# CoolRoof_Terminal_exterieur.net
KiCad netlist of a schematic drawn in EAGLE
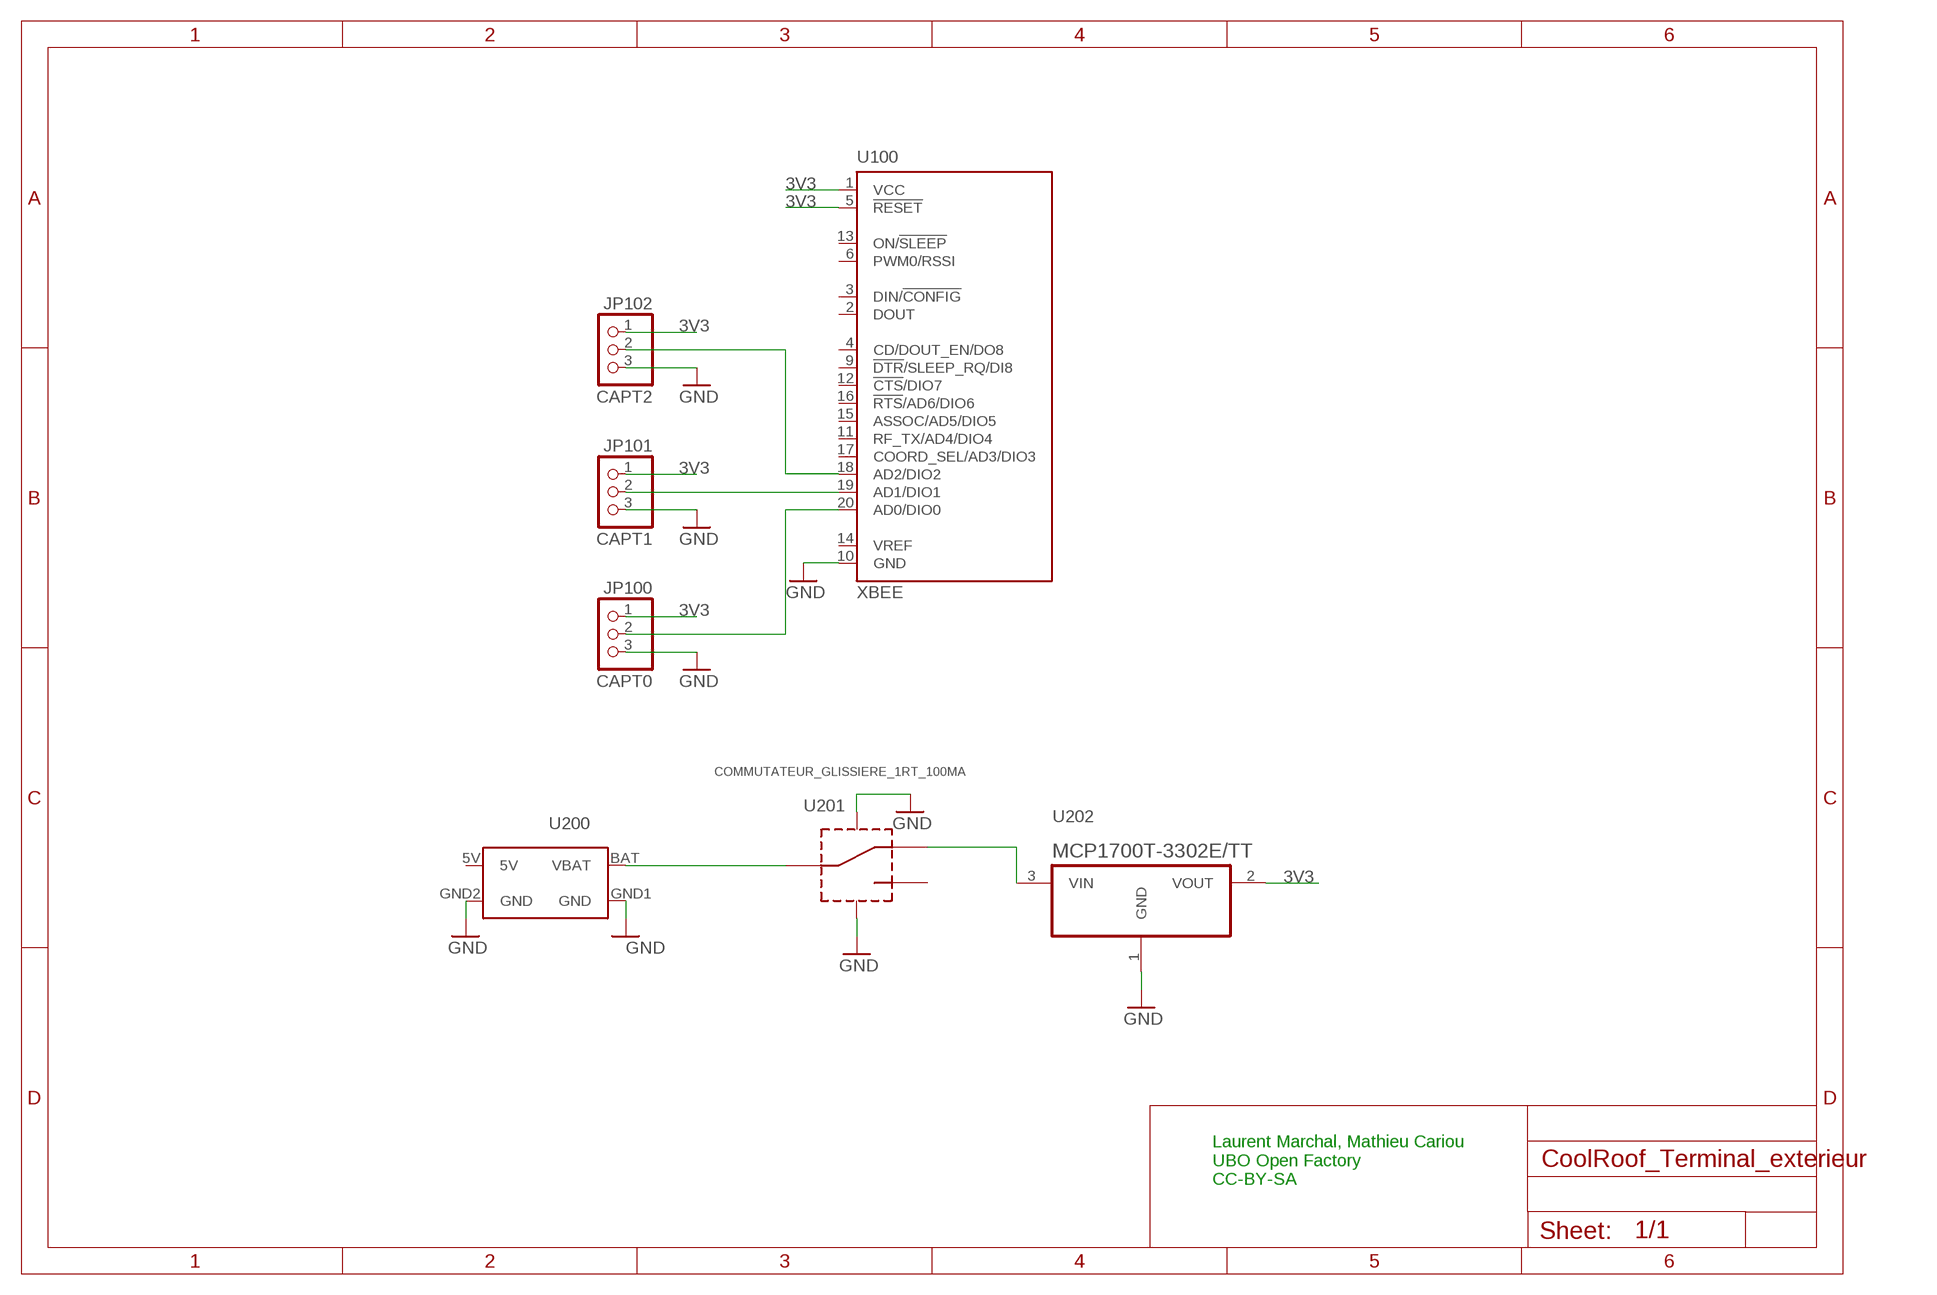
[diagram p0: schematic, sheet 1]

(export (version "E")
  (design (tool "Eeschema 10.0.6"))
  (components
    (comp (ref "JP100")
      (value "CAPT0")
      (footprint "eagle-import:1X03")
      (libsource (lib "eagle-import") (part "PINHD-1X3"))
    )
    (comp (ref "JP101")
      (value "CAPT1")
      (footprint "eagle-import:1X03")
      (libsource (lib "eagle-import") (part "PINHD-1X3"))
    )
    (comp (ref "JP102")
      (value "CAPT2")
      (footprint "eagle-import:1X03")
      (libsource (lib "eagle-import") (part "PINHD-1X3"))
    )
    (comp (ref "U100")
      (value "XBEE")
      (footprint "eagle-import:XBEE")
      (fields (field (name "MPN") "XBP24-Z7UIT-004"))
      (libsource (lib "eagle-import") (part "XBEE"))
    )
    (comp (ref "U200")
      (value "MICROUSB-LIPO-CHARGEUR-ADAFRUITMICRO-USB-CHARGEUR")
      (footprint "eagle-import:MICROUSB-LIPO-CHARGEUR-ADAFRUIT")
      (libsource (lib "eagle-import") (part "MICROUSB-LIPO-CHARGEUR-ADAFRUITMICRO-USB-CHARGEUR"))
    )
    (comp (ref "U201")
      (value "COMMUTATEUR_GLISSIERE_1RT_100MA")
      (footprint "eagle-import:COMMUTATEUR_GLISSIERE_1RT_100MA")
      (libsource (lib "eagle-import") (part "COMMUTATEUR_GLISSIERE_1RT_100MA"))
    )
    (comp (ref "U202")
      (value "MCP1700T-3302E/TT")
      (footprint "eagle-import:SOT95P237X112-3N")
      (fields (field (name "MF") "Microchip Technology"))
      (libsource (lib "eagle-import") (part "MCP1700T-3302E/TT"))
    )
  )
  (nets
    (net (code "1") (name "/3V3") (class "Default")
      (node (ref "JP100") (pin "1") (pinfunction "1_1") (pintype "passive"))
      (node (ref "JP101") (pin "1") (pinfunction "1_1") (pintype "passive"))
      (node (ref "JP102") (pin "1") (pinfunction "1_1") (pintype "passive"))
      (node (ref "U100") (pin "1") (pinfunction "VCC_1") (pintype "power_in"))
      (node (ref "U100") (pin "5") (pinfunction "~{RESET}_5") (pintype "input"))
      (node (ref "U202") (pin "2") (pinfunction "VOUT_2") (pintype "output"))
    )
    (net (code "2") (name "GND") (class "Default")
      (node (ref "JP100") (pin "3") (pinfunction "3_3") (pintype "passive"))
      (node (ref "JP101") (pin "3") (pinfunction "3_3") (pintype "passive"))
      (node (ref "JP102") (pin "3") (pinfunction "3_3") (pintype "passive"))
      (node (ref "U100") (pin "10") (pinfunction "GND_10") (pintype "power_in"))
      (node (ref "U200") (pin "GND1") (pinfunction "GND_GND1") (pintype "bidirectional"))
      (node (ref "U200") (pin "GND2") (pinfunction "GND_GND2") (pintype "bidirectional"))
      (node (ref "U201") (pin "GNDA") (pinfunction "GNDA_GNDA") (pintype "bidirectional"))
      (node (ref "U201") (pin "GNDB") (pinfunction "GNDB_GNDB") (pintype "bidirectional"))
      (node (ref "U202") (pin "1") (pinfunction "GND_1") (pintype "power_in"))
    )
    (net (code "3") (name "Net-(U100-AD0{slash}DIO0)") (class "Default")
      (node (ref "JP100") (pin "2") (pinfunction "2_2") (pintype "passive"))
      (node (ref "U100") (pin "20") (pinfunction "AD0/DIO0_20") (pintype "bidirectional"))
    )
    (net (code "4") (name "Net-(U100-AD1{slash}DIO1)") (class "Default")
      (node (ref "JP101") (pin "2") (pinfunction "2_2") (pintype "passive"))
      (node (ref "U100") (pin "19") (pinfunction "AD1/DIO1_19") (pintype "bidirectional"))
    )
    (net (code "5") (name "Net-(U100-AD2{slash}DIO2)") (class "Default")
      (node (ref "JP102") (pin "2") (pinfunction "2_2") (pintype "passive"))
      (node (ref "U100") (pin "18") (pinfunction "AD2/DIO2_18") (pintype "bidirectional"))
    )
    (net (code "6") (name "Net-(U200-VBAT)") (class "Default")
      (node (ref "U200") (pin "BAT") (pinfunction "VBAT_BAT") (pintype "bidirectional"))
      (node (ref "U201") (pin "COM") (pinfunction "COM_COM") (pintype "bidirectional"))
    )
    (net (code "7") (name "Net-(U201-OUT2)") (class "Default")
      (node (ref "U201") (pin "OUTB") (pinfunction "OUT2_OUTB") (pintype "bidirectional"))
      (node (ref "U202") (pin "3") (pinfunction "VIN_3") (pintype "input"))
    )
    (net (code "8") (name "unconnected-(U100-ASSOC{slash}AD5{slash}DIO5-Pad15)") (class "Default")
      (node (ref "U100") (pin "15") (pinfunction "ASSOC/AD5/DIO5_15") (pintype "bidirectional"))
    )
    (net (code "9") (name "unconnected-(U100-CD{slash}DOUT_EN{slash}DO8-Pad4)") (class "Default")
      (node (ref "U100") (pin "4") (pinfunction "CD/DOUT_EN/DO8_4") (pintype "output"))
    )
    (net (code "10") (name "unconnected-(U100-COORD_SEL{slash}AD3{slash}DIO3-Pad17)") (class "Default")
      (node (ref "U100") (pin "17") (pinfunction "COORD_SEL/AD3/DIO3_17") (pintype "bidirectional"))
    )
    (net (code "11") (name "unconnected-(U100-DIN{slash}~{CONFIG}-Pad3)") (class "Default")
      (node (ref "U100") (pin "3") (pinfunction "DIN/~{CONFIG}_3") (pintype "input"))
    )
    (net (code "12") (name "unconnected-(U100-DOUT-Pad2)") (class "Default")
      (node (ref "U100") (pin "2") (pinfunction "DOUT_2") (pintype "output"))
    )
    (net (code "13") (name "unconnected-(U100-ON{slash}~{SLEEP}-Pad13)") (class "Default")
      (node (ref "U100") (pin "13") (pinfunction "ON/~{SLEEP}_13") (pintype "output"))
    )
    (net (code "14") (name "unconnected-(U100-PWM0{slash}RSSI-Pad6)") (class "Default")
      (node (ref "U100") (pin "6") (pinfunction "PWM0/RSSI_6") (pintype "output"))
    )
    (net (code "15") (name "unconnected-(U100-RF_TX{slash}AD4{slash}DIO4-Pad11)") (class "Default")
      (node (ref "U100") (pin "11") (pinfunction "RF_TX/AD4/DIO4_11") (pintype "bidirectional"))
    )
    (net (code "16") (name "unconnected-(U100-VREF-Pad14)") (class "Default")
      (node (ref "U100") (pin "14") (pinfunction "VREF_14") (pintype "input"))
    )
    (net (code "17") (name "unconnected-(U100-~{CTS}{slash}DIO7-Pad12)") (class "Default")
      (node (ref "U100") (pin "12") (pinfunction "~{CTS}/DIO7_12") (pintype "bidirectional"))
    )
    (net (code "18") (name "unconnected-(U100-~{DTR}{slash}SLEEP_RQ{slash}DI8-Pad9)") (class "Default")
      (node (ref "U100") (pin "9") (pinfunction "~{DTR}/SLEEP_RQ/DI8_9") (pintype "bidirectional"))
    )
    (net (code "19") (name "unconnected-(U100-~{RTS}{slash}AD6{slash}DIO6-Pad16)") (class "Default")
      (node (ref "U100") (pin "16") (pinfunction "~{RTS}/AD6/DIO6_16") (pintype "bidirectional"))
    )
    (net (code "20") (name "unconnected-(U200-Pad5V)") (class "Default")
      (node (ref "U200") (pin "5V") (pinfunction "5V_5V") (pintype "bidirectional"))
    )
    (net (code "21") (name "unconnected-(U201-OUT1-PadOUTA)") (class "Default")
      (node (ref "U201") (pin "OUTA") (pinfunction "OUT1_OUTA") (pintype "bidirectional"))
    )
  )
)
